# uav_router.net
KiCad netlist of a schematic drawn in EAGLE
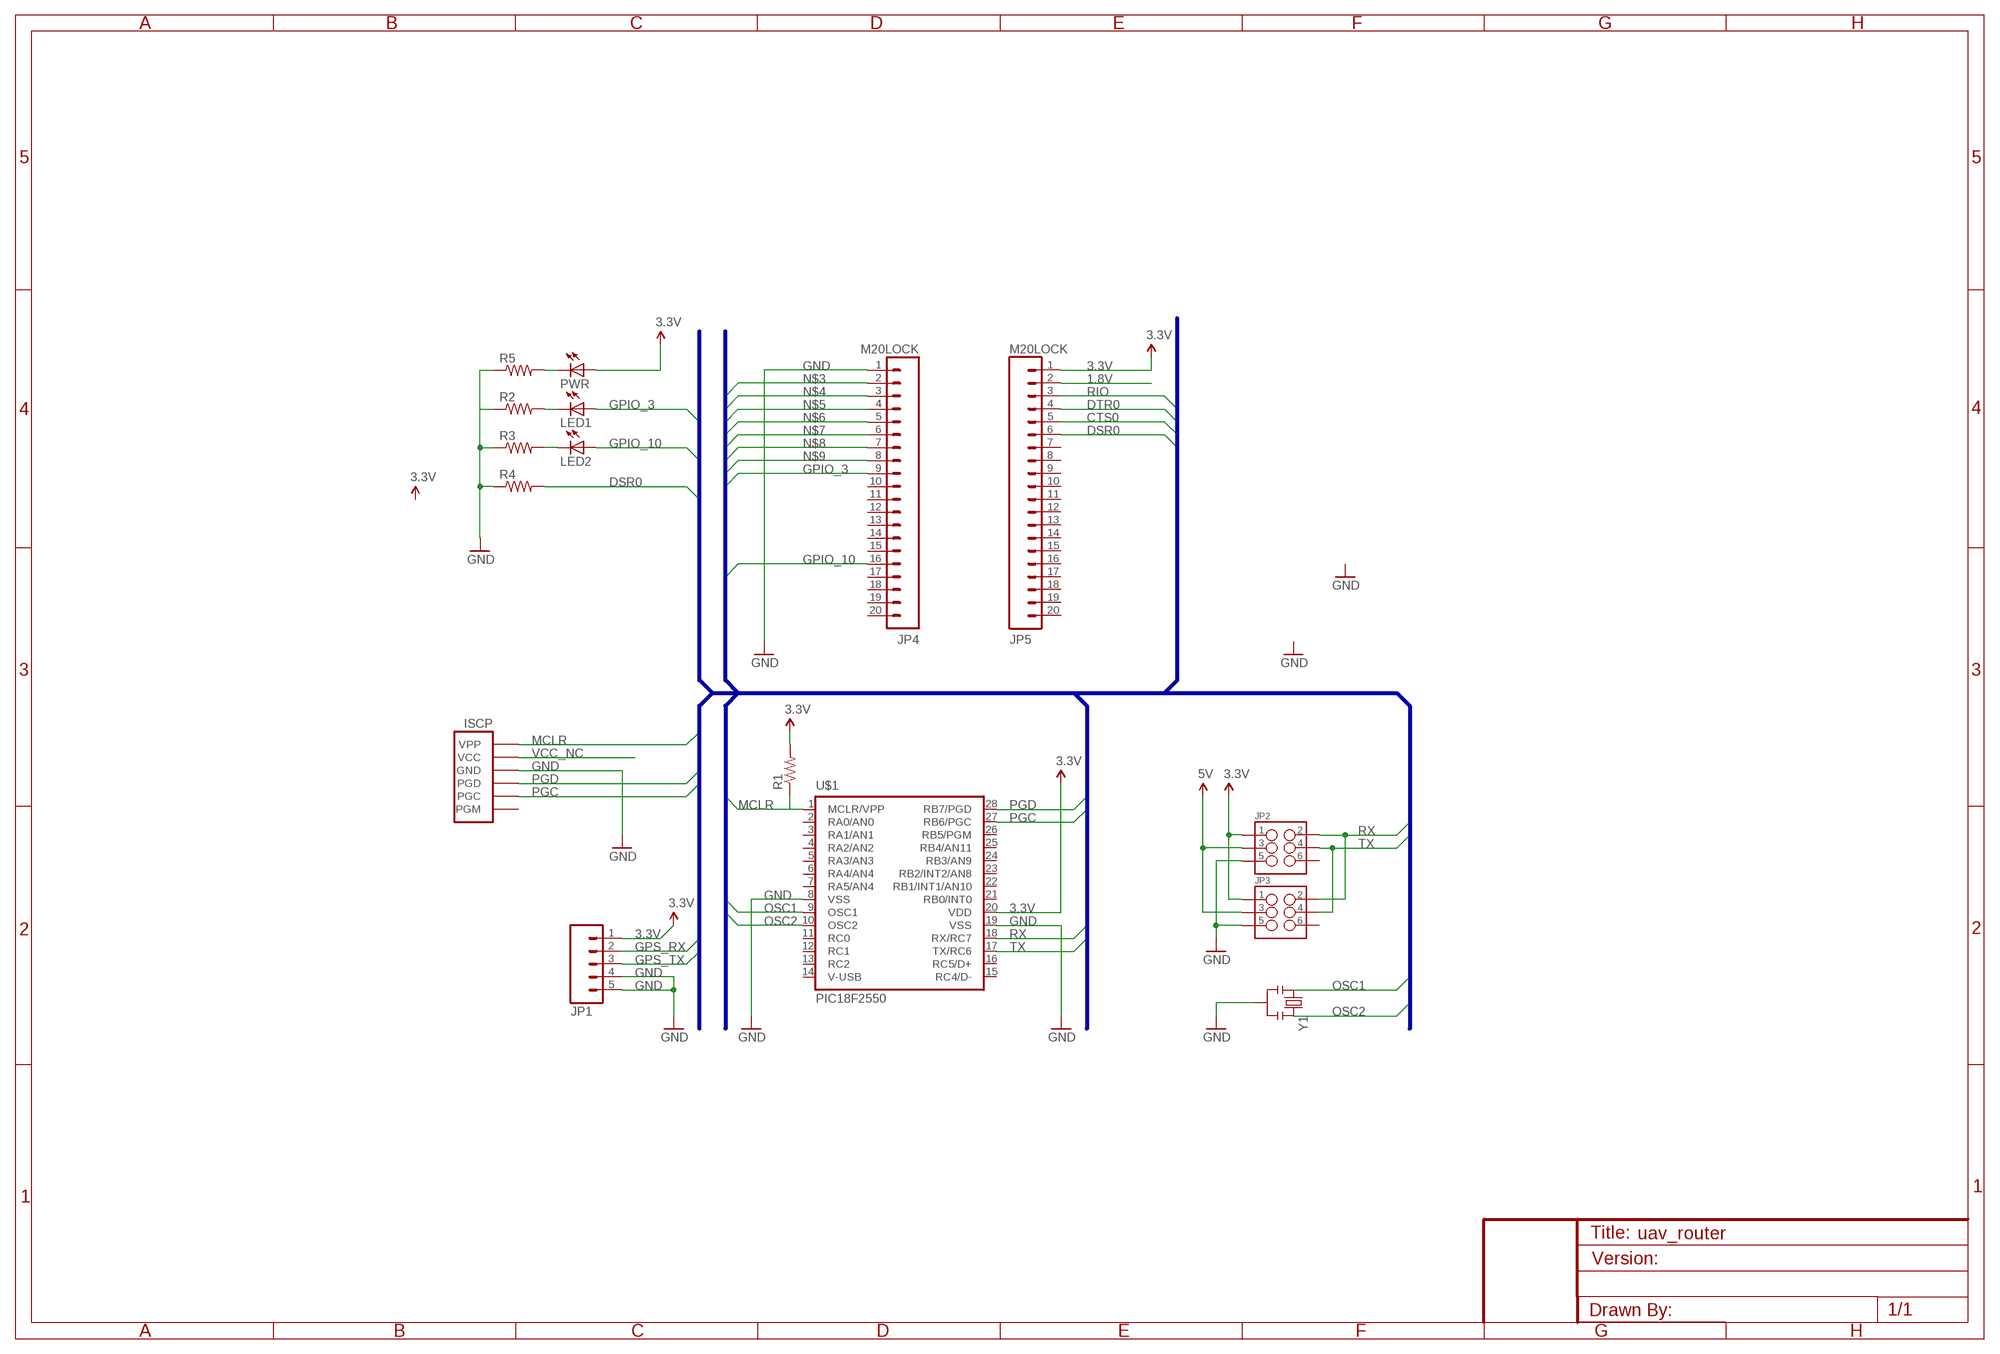
[diagram p0: schematic, sheet 1]

(export (version "E")
  (design (tool "Eeschema 10.0.6"))
  (components
    (comp (ref "ISCP")
      (value "PIC-ICSPPOLAR_LOCK")
      (footprint "eagle-import:MOLEX-1X6_LOCK")
      (libsource (lib "eagle-import") (part "PIC-ICSPPOLAR_LOCK"))
    )
    (comp (ref "JP1")
      (value "M05LOCK")
      (footprint "eagle-import:1X05_LOCK")
      (libsource (lib "eagle-import") (part "M05LOCK"))
    )
    (comp (ref "JP2")
      (value "M03X2")
      (footprint "eagle-import:2X3-SHROUDED")
      (libsource (lib "eagle-import") (part "M03X2"))
    )
    (comp (ref "JP3")
      (value "M03X2")
      (footprint "eagle-import:2X3-SHROUDED")
      (libsource (lib "eagle-import") (part "M03X2"))
    )
    (comp (ref "JP4")
      (value "M20LOCK")
      (footprint "eagle-import:1X20_LOCK")
      (libsource (lib "eagle-import") (part "M20LOCK"))
    )
    (comp (ref "JP5")
      (value "M20LOCK")
      (footprint "eagle-import:1X20_LOCK")
      (libsource (lib "eagle-import") (part "M20LOCK"))
    )
    (comp (ref "LED1")
      (value "LED5MM")
      (footprint "eagle-import:LED5MM")
      (libsource (lib "eagle-import") (part "LED5MM"))
    )
    (comp (ref "LED2")
      (value "LED5MM")
      (footprint "eagle-import:LED5MM")
      (libsource (lib "eagle-import") (part "LED5MM"))
    )
    (comp (ref "PWR")
      (value "LED5MM")
      (footprint "eagle-import:LED5MM")
      (libsource (lib "eagle-import") (part "LED5MM"))
    )
    (comp (ref "R1")
      (value "RESISTORKIT")
      (footprint "eagle-import:AXIAL-0.3-KIT")
      (libsource (lib "eagle-import") (part "RESISTORKIT"))
    )
    (comp (ref "R2")
      (value "RESISTORKIT")
      (footprint "eagle-import:AXIAL-0.3-KIT")
      (libsource (lib "eagle-import") (part "RESISTORKIT"))
    )
    (comp (ref "R3")
      (value "RESISTORKIT")
      (footprint "eagle-import:AXIAL-0.3-KIT")
      (libsource (lib "eagle-import") (part "RESISTORKIT"))
    )
    (comp (ref "R4")
      (value "RESISTORKIT")
      (footprint "eagle-import:AXIAL-0.3-KIT")
      (libsource (lib "eagle-import") (part "RESISTORKIT"))
    )
    (comp (ref "R5")
      (value "RESISTORKIT")
      (footprint "eagle-import:AXIAL-0.3-KIT")
      (libsource (lib "eagle-import") (part "RESISTORKIT"))
    )
    (comp (ref "U$1")
      (value "PIC18F2550")
      (footprint "eagle-import:DIL28-3")
      (libsource (lib "eagle-import") (part "PIC18F2550"))
    )
    (comp (ref "Y1")
      (value "RESONATORPTH")
      (footprint "eagle-import:RESONATOR-PTH")
      (libsource (lib "eagle-import") (part "RESONATORPTH"))
    )
  )
  (nets
    (net (code "1") (name "/1.8V") (class "Default")
      (node (ref "JP5") (pin "2") (pinfunction "2_2") (pintype "passive"))
    )
    (net (code "2") (name "/CTS0") (class "Default")
      (node (ref "JP5") (pin "5") (pinfunction "5_5") (pintype "passive"))
    )
    (net (code "3") (name "/DSR0") (class "Default")
      (node (ref "JP5") (pin "6") (pinfunction "6_6") (pintype "passive"))
      (node (ref "R4") (pin "P$2") (pinfunction "2_P$2") (pintype "passive"))
    )
    (net (code "4") (name "/DTR0") (class "Default")
      (node (ref "JP5") (pin "4") (pinfunction "4_4") (pintype "passive"))
    )
    (net (code "5") (name "/GPIO_3") (class "Default")
      (node (ref "JP4") (pin "9") (pinfunction "9_9") (pintype "passive"))
      (node (ref "LED1") (pin "A") (pinfunction "A_A") (pintype "passive"))
    )
    (net (code "6") (name "/GPIO_10") (class "Default")
      (node (ref "JP4") (pin "16") (pinfunction "16_16") (pintype "passive"))
      (node (ref "LED2") (pin "A") (pinfunction "A_A") (pintype "passive"))
    )
    (net (code "7") (name "/GPS_RX") (class "Default")
      (node (ref "JP1") (pin "2") (pinfunction "2_2") (pintype "passive"))
    )
    (net (code "8") (name "/GPS_TX") (class "Default")
      (node (ref "JP1") (pin "3") (pinfunction "3_3") (pintype "passive"))
    )
    (net (code "9") (name "/MCLR") (class "Default")
      (node (ref "ISCP") (pin "6") (pinfunction "VPP_6") (pintype "bidirectional"))
      (node (ref "R1") (pin "P$1") (pinfunction "1_P$1") (pintype "passive"))
      (node (ref "U$1") (pin "1") (pinfunction "MCLR/VPP_1") (pintype "bidirectional"))
    )
    (net (code "10") (name "/N$3") (class "Default")
      (node (ref "JP4") (pin "2") (pinfunction "2_2") (pintype "passive"))
    )
    (net (code "11") (name "/N$4") (class "Default")
      (node (ref "JP4") (pin "3") (pinfunction "3_3") (pintype "passive"))
    )
    (net (code "12") (name "/N$5") (class "Default")
      (node (ref "JP4") (pin "4") (pinfunction "4_4") (pintype "passive"))
    )
    (net (code "13") (name "/N$6") (class "Default")
      (node (ref "JP4") (pin "5") (pinfunction "5_5") (pintype "passive"))
    )
    (net (code "14") (name "/N$7") (class "Default")
      (node (ref "JP4") (pin "6") (pinfunction "6_6") (pintype "passive"))
    )
    (net (code "15") (name "/N$8") (class "Default")
      (node (ref "JP4") (pin "7") (pinfunction "7_7") (pintype "passive"))
    )
    (net (code "16") (name "/N$9") (class "Default")
      (node (ref "JP4") (pin "8") (pinfunction "8_8") (pintype "passive"))
    )
    (net (code "17") (name "/OSC1") (class "Default")
      (node (ref "U$1") (pin "9") (pinfunction "OSC1_9") (pintype "bidirectional"))
      (node (ref "Y1") (pin "1") (pinfunction "1_1") (pintype "passive"))
    )
    (net (code "18") (name "/OSC2") (class "Default")
      (node (ref "U$1") (pin "10") (pinfunction "OSC2_10") (pintype "bidirectional"))
      (node (ref "Y1") (pin "3") (pinfunction "3_3") (pintype "passive"))
    )
    (net (code "19") (name "/PGC") (class "Default")
      (node (ref "ISCP") (pin "2") (pinfunction "PGC_2") (pintype "bidirectional"))
      (node (ref "U$1") (pin "27") (pinfunction "RB6/PGC_27") (pintype "bidirectional"))
    )
    (net (code "20") (name "/PGD") (class "Default")
      (node (ref "ISCP") (pin "3") (pinfunction "PGD_3") (pintype "bidirectional"))
      (node (ref "U$1") (pin "28") (pinfunction "RB7/PGD_28") (pintype "bidirectional"))
    )
    (net (code "21") (name "/RIO") (class "Default")
      (node (ref "JP5") (pin "3") (pinfunction "3_3") (pintype "passive"))
    )
    (net (code "22") (name "/RX") (class "Default")
      (node (ref "JP2") (pin "2") (pinfunction "2_2") (pintype "bidirectional"))
      (node (ref "JP3") (pin "2") (pinfunction "2_2") (pintype "bidirectional"))
      (node (ref "U$1") (pin "18") (pinfunction "RX/RC7_18") (pintype "input"))
    )
    (net (code "23") (name "/TX") (class "Default")
      (node (ref "JP2") (pin "4") (pinfunction "4_4") (pintype "bidirectional"))
      (node (ref "JP3") (pin "4") (pinfunction "4_4") (pintype "bidirectional"))
      (node (ref "U$1") (pin "17") (pinfunction "TX/RC6_17") (pintype "bidirectional"))
    )
    (net (code "24") (name "/VCC_NC") (class "Default")
      (node (ref "ISCP") (pin "5") (pinfunction "VCC_5") (pintype "bidirectional"))
    )
    (net (code "25") (name "3.3V") (class "Default")
      (node (ref "JP1") (pin "1") (pinfunction "1_1") (pintype "passive"))
      (node (ref "JP2") (pin "1") (pinfunction "1_1") (pintype "bidirectional"))
      (node (ref "JP3") (pin "1") (pinfunction "1_1") (pintype "bidirectional"))
      (node (ref "JP5") (pin "1") (pinfunction "1_1") (pintype "passive"))
      (node (ref "PWR") (pin "A") (pinfunction "A_A") (pintype "passive"))
      (node (ref "R1") (pin "P$2") (pinfunction "2_P$2") (pintype "passive"))
      (node (ref "U$1") (pin "20") (pinfunction "VDD_20") (pintype "power_in"))
    )
    (net (code "26") (name "5V") (class "Default")
      (node (ref "JP2") (pin "3") (pinfunction "3_3") (pintype "bidirectional"))
      (node (ref "JP3") (pin "3") (pinfunction "3_3") (pintype "bidirectional"))
    )
    (net (code "27") (name "GND") (class "Default")
      (node (ref "ISCP") (pin "4") (pinfunction "GND_4") (pintype "bidirectional"))
      (node (ref "JP1") (pin "4") (pinfunction "4_4") (pintype "passive"))
      (node (ref "JP1") (pin "5") (pinfunction "5_5") (pintype "passive"))
      (node (ref "JP2") (pin "5") (pinfunction "5_5") (pintype "bidirectional"))
      (node (ref "JP3") (pin "5") (pinfunction "5_5") (pintype "bidirectional"))
      (node (ref "JP4") (pin "1") (pinfunction "1_1") (pintype "passive"))
      (node (ref "R2") (pin "P$1") (pinfunction "1_P$1") (pintype "passive"))
      (node (ref "R3") (pin "P$1") (pinfunction "1_P$1") (pintype "passive"))
      (node (ref "R4") (pin "P$1") (pinfunction "1_P$1") (pintype "passive"))
      (node (ref "R5") (pin "P$1") (pinfunction "1_P$1") (pintype "passive"))
      (node (ref "U$1") (pin "19") (pinfunction "VSS_19") (pintype "power_in"))
      (node (ref "U$1") (pin "8") (pinfunction "VSS_8") (pintype "power_in"))
      (node (ref "Y1") (pin "2") (pinfunction "2_2") (pintype "passive"))
    )
    (net (code "28") (name "Net-(LED1-C)") (class "Default")
      (node (ref "LED1") (pin "K") (pinfunction "C_K") (pintype "passive"))
      (node (ref "R2") (pin "P$2") (pinfunction "2_P$2") (pintype "passive"))
    )
    (net (code "29") (name "Net-(LED2-C)") (class "Default")
      (node (ref "LED2") (pin "K") (pinfunction "C_K") (pintype "passive"))
      (node (ref "R3") (pin "P$2") (pinfunction "2_P$2") (pintype "passive"))
    )
    (net (code "30") (name "Net-(PWR-C)") (class "Default")
      (node (ref "PWR") (pin "K") (pinfunction "C_K") (pintype "passive"))
      (node (ref "R5") (pin "P$2") (pinfunction "2_P$2") (pintype "passive"))
    )
    (net (code "31") (name "unconnected-(ISCP-PGM-Pad1)") (class "Default")
      (node (ref "ISCP") (pin "1") (pinfunction "PGM_1") (pintype "bidirectional"))
    )
    (net (code "32") (name "unconnected-(JP2-Pad6)") (class "Default")
      (node (ref "JP2") (pin "6") (pinfunction "6_6") (pintype "bidirectional"))
    )
    (net (code "33") (name "unconnected-(JP3-Pad6)") (class "Default")
      (node (ref "JP3") (pin "6") (pinfunction "6_6") (pintype "bidirectional"))
    )
    (net (code "34") (name "unconnected-(JP4-Pad10)") (class "Default")
      (node (ref "JP4") (pin "10") (pinfunction "10_10") (pintype "passive"))
    )
    (net (code "35") (name "unconnected-(JP4-Pad11)") (class "Default")
      (node (ref "JP4") (pin "11") (pinfunction "11_11") (pintype "passive"))
    )
    (net (code "36") (name "unconnected-(JP4-Pad12)") (class "Default")
      (node (ref "JP4") (pin "12") (pinfunction "12_12") (pintype "passive"))
    )
    (net (code "37") (name "unconnected-(JP4-Pad13)") (class "Default")
      (node (ref "JP4") (pin "13") (pinfunction "13_13") (pintype "passive"))
    )
    (net (code "38") (name "unconnected-(JP4-Pad14)") (class "Default")
      (node (ref "JP4") (pin "14") (pinfunction "14_14") (pintype "passive"))
    )
    (net (code "39") (name "unconnected-(JP4-Pad15)") (class "Default")
      (node (ref "JP4") (pin "15") (pinfunction "15_15") (pintype "passive"))
    )
    (net (code "40") (name "unconnected-(JP4-Pad17)") (class "Default")
      (node (ref "JP4") (pin "17") (pinfunction "17_17") (pintype "passive"))
    )
    (net (code "41") (name "unconnected-(JP4-Pad18)") (class "Default")
      (node (ref "JP4") (pin "18") (pinfunction "18_18") (pintype "passive"))
    )
    (net (code "42") (name "unconnected-(JP4-Pad19)") (class "Default")
      (node (ref "JP4") (pin "19") (pinfunction "19_19") (pintype "passive"))
    )
    (net (code "43") (name "unconnected-(JP4-Pad20)") (class "Default")
      (node (ref "JP4") (pin "20") (pinfunction "20_20") (pintype "passive"))
    )
    (net (code "44") (name "unconnected-(JP5-Pad7)") (class "Default")
      (node (ref "JP5") (pin "7") (pinfunction "7_7") (pintype "passive"))
    )
    (net (code "45") (name "unconnected-(JP5-Pad8)") (class "Default")
      (node (ref "JP5") (pin "8") (pinfunction "8_8") (pintype "passive"))
    )
    (net (code "46") (name "unconnected-(JP5-Pad9)") (class "Default")
      (node (ref "JP5") (pin "9") (pinfunction "9_9") (pintype "passive"))
    )
    (net (code "47") (name "unconnected-(JP5-Pad10)") (class "Default")
      (node (ref "JP5") (pin "10") (pinfunction "10_10") (pintype "passive"))
    )
    (net (code "48") (name "unconnected-(JP5-Pad11)") (class "Default")
      (node (ref "JP5") (pin "11") (pinfunction "11_11") (pintype "passive"))
    )
    (net (code "49") (name "unconnected-(JP5-Pad12)") (class "Default")
      (node (ref "JP5") (pin "12") (pinfunction "12_12") (pintype "passive"))
    )
    (net (code "50") (name "unconnected-(JP5-Pad13)") (class "Default")
      (node (ref "JP5") (pin "13") (pinfunction "13_13") (pintype "passive"))
    )
    (net (code "51") (name "unconnected-(JP5-Pad14)") (class "Default")
      (node (ref "JP5") (pin "14") (pinfunction "14_14") (pintype "passive"))
    )
    (net (code "52") (name "unconnected-(JP5-Pad15)") (class "Default")
      (node (ref "JP5") (pin "15") (pinfunction "15_15") (pintype "passive"))
    )
    (net (code "53") (name "unconnected-(JP5-Pad16)") (class "Default")
      (node (ref "JP5") (pin "16") (pinfunction "16_16") (pintype "passive"))
    )
    (net (code "54") (name "unconnected-(JP5-Pad17)") (class "Default")
      (node (ref "JP5") (pin "17") (pinfunction "17_17") (pintype "passive"))
    )
    (net (code "55") (name "unconnected-(JP5-Pad18)") (class "Default")
      (node (ref "JP5") (pin "18") (pinfunction "18_18") (pintype "passive"))
    )
    (net (code "56") (name "unconnected-(JP5-Pad19)") (class "Default")
      (node (ref "JP5") (pin "19") (pinfunction "19_19") (pintype "passive"))
    )
    (net (code "57") (name "unconnected-(JP5-Pad20)") (class "Default")
      (node (ref "JP5") (pin "20") (pinfunction "20_20") (pintype "passive"))
    )
    (net (code "58") (name "unconnected-(U$1-RA0{slash}AN0-Pad2)") (class "Default")
      (node (ref "U$1") (pin "2") (pinfunction "RA0/AN0_2") (pintype "bidirectional"))
    )
    (net (code "59") (name "unconnected-(U$1-RA1{slash}AN1-Pad3)") (class "Default")
      (node (ref "U$1") (pin "3") (pinfunction "RA1/AN1_3") (pintype "bidirectional"))
    )
    (net (code "60") (name "unconnected-(U$1-RA2{slash}AN2-Pad4)") (class "Default")
      (node (ref "U$1") (pin "4") (pinfunction "RA2/AN2_4") (pintype "bidirectional"))
    )
    (net (code "61") (name "unconnected-(U$1-RA3{slash}AN3-Pad5)") (class "Default")
      (node (ref "U$1") (pin "5") (pinfunction "RA3/AN3_5") (pintype "bidirectional"))
    )
    (net (code "62") (name "unconnected-(U$1-RA4{slash}AN4-Pad6)") (class "Default")
      (node (ref "U$1") (pin "6") (pinfunction "RA4/AN4_6") (pintype "bidirectional"))
    )
    (net (code "63") (name "unconnected-(U$1-RA5{slash}AN4-Pad7)") (class "Default")
      (node (ref "U$1") (pin "7") (pinfunction "RA5/AN4_7") (pintype "bidirectional"))
    )
    (net (code "64") (name "unconnected-(U$1-RB0{slash}INT0-Pad21)") (class "Default")
      (node (ref "U$1") (pin "21") (pinfunction "RB0/INT0_21") (pintype "bidirectional"))
    )
    (net (code "65") (name "unconnected-(U$1-RB1{slash}INT1{slash}AN10-Pad22)") (class "Default")
      (node (ref "U$1") (pin "22") (pinfunction "RB1/INT1/AN10_22") (pintype "bidirectional"))
    )
    (net (code "66") (name "unconnected-(U$1-RB2{slash}INT2{slash}AN8-Pad23)") (class "Default")
      (node (ref "U$1") (pin "23") (pinfunction "RB2/INT2/AN8_23") (pintype "bidirectional"))
    )
    (net (code "67") (name "unconnected-(U$1-RB3{slash}AN9-Pad24)") (class "Default")
      (node (ref "U$1") (pin "24") (pinfunction "RB3/AN9_24") (pintype "bidirectional"))
    )
    (net (code "68") (name "unconnected-(U$1-RB4{slash}AN11-Pad25)") (class "Default")
      (node (ref "U$1") (pin "25") (pinfunction "RB4/AN11_25") (pintype "bidirectional"))
    )
    (net (code "69") (name "unconnected-(U$1-RB5{slash}PGM-Pad26)") (class "Default")
      (node (ref "U$1") (pin "26") (pinfunction "RB5/PGM_26") (pintype "bidirectional"))
    )
    (net (code "70") (name "unconnected-(U$1-RC0-Pad11)") (class "Default")
      (node (ref "U$1") (pin "11") (pinfunction "RC0_11") (pintype "bidirectional"))
    )
    (net (code "71") (name "unconnected-(U$1-RC1-Pad12)") (class "Default")
      (node (ref "U$1") (pin "12") (pinfunction "RC1_12") (pintype "bidirectional"))
    )
    (net (code "72") (name "unconnected-(U$1-RC2-Pad13)") (class "Default")
      (node (ref "U$1") (pin "13") (pinfunction "RC2_13") (pintype "bidirectional"))
    )
    (net (code "73") (name "unconnected-(U$1-RC4{slash}D--Pad15)") (class "Default")
      (node (ref "U$1") (pin "15") (pinfunction "RC4/D-_15") (pintype "bidirectional"))
    )
    (net (code "74") (name "unconnected-(U$1-RC5{slash}D+-Pad16)") (class "Default")
      (node (ref "U$1") (pin "16") (pinfunction "RC5/D+_16") (pintype "bidirectional"))
    )
    (net (code "75") (name "unconnected-(U$1-V-USB-Pad14)") (class "Default")
      (node (ref "U$1") (pin "14") (pinfunction "V-USB_14") (pintype "bidirectional"))
    )
  )
)
